# PC2_Input.net
KiCad netlist of a schematic drawn in Altium Designer
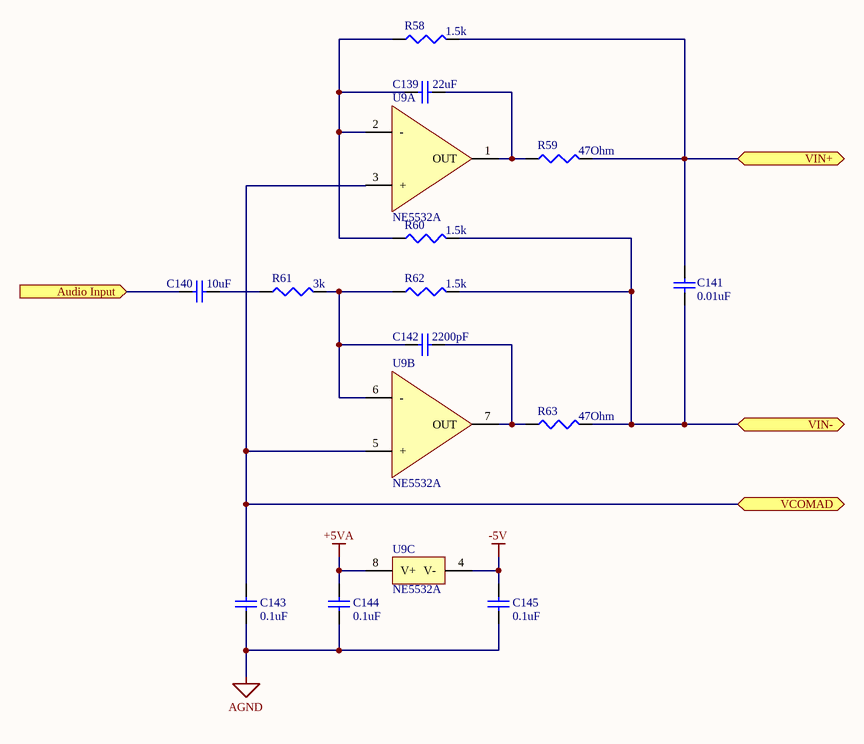
[diagram p0: PC2_Input.SchDoc]

(export (version "E")
  (design (tool "Eeschema 10.0.6"))
  (components
    (comp (ref "C139")
      (value "22uF")
      (footprint "CAPC1608X08")
      (description "Capacitor (Semiconductor SIM Model)")
      (libsource (lib "Michel") (part "Cap Semi"))
    )
    (comp (ref "C140")
      (value "10uF")
      (footprint "CAPC1608X08")
      (description "Capacitor (Semiconductor SIM Model)")
      (libsource (lib "Michel") (part "Cap Semi"))
    )
    (comp (ref "C141")
      (value "0.01uF")
      (footprint "CAPC1608X08")
      (description "Capacitor (Semiconductor SIM Model)")
      (fields (field (name "Comment") "Cap Semi"))
      (libsource (lib "Michel") (part "Cap Semi"))
    )
    (comp (ref "C142")
      (value "2200pF")
      (footprint "CAPC1608X08")
      (description "Capacitor (Semiconductor SIM Model)")
      (fields (field (name "Comment") "Cap Semi"))
      (libsource (lib "Michel") (part "Cap Semi"))
    )
    (comp (ref "C143")
      (value "0.1uF")
      (footprint "CAPC1608X08")
      (description "Capacitor (Semiconductor SIM Model)")
      (libsource (lib "Michel") (part "Cap Semi"))
    )
    (comp (ref "C144")
      (value "0.1uF")
      (footprint "CAPC1608X08")
      (description "Capacitor (Semiconductor SIM Model)")
      (libsource (lib "Michel") (part "Cap Semi"))
    )
    (comp (ref "C145")
      (value "0.1uF")
      (footprint "CAPC1608X08")
      (description "Capacitor (Semiconductor SIM Model)")
      (libsource (lib "Michel") (part "Cap Semi"))
    )
    (comp (ref "R58")
      (value "1.5k")
      (footprint "RESC1608X05")
      (description "Resistor")
      (fields (field (name "Comment") "Res3"))
      (libsource (lib "Michel") (part "Res3"))
    )
    (comp (ref "R59")
      (value "47Ohm")
      (footprint "RESC1608X05")
      (description "Resistor")
      (fields (field (name "Comment") "Res3"))
      (libsource (lib "Michel") (part "Res3"))
    )
    (comp (ref "R60")
      (value "1.5k")
      (footprint "RESC1608X05")
      (description "Resistor")
      (fields (field (name "Comment") "Res3"))
      (libsource (lib "Michel") (part "Res3"))
    )
    (comp (ref "R61")
      (value "3k")
      (footprint "RESC1608X05")
      (description "Resistor")
      (fields (field (name "Comment") "Res3"))
      (libsource (lib "Michel") (part "Res3"))
    )
    (comp (ref "R62")
      (value "1.5k")
      (footprint "RESC1608X05")
      (description "Resistor")
      (fields (field (name "Comment") "Res3"))
      (libsource (lib "Michel") (part "Res3"))
    )
    (comp (ref "R63")
      (value "47Ohm")
      (footprint "RESC1608X05")
      (description "Resistor")
      (fields (field (name "Comment") "Res3"))
      (libsource (lib "Michel") (part "Res3"))
    )
    (comp (ref "U9")
      (value "NE5532A")
      (footprint "D8-M")
      (description "Amplificateur Opérationnel")
      (libsource (lib "Michel") (part "NE5532A"))
    )
  )
  (nets
    (net (code "1") (name "+5VA") (class "Default")
      (node (ref "C144") (pin "1") (pinfunction "1_1") (pintype "passive"))
      (node (ref "U9") (pin "8") (pinfunction "V+_8") (pintype "passive"))
    )
    (net (code "2") (name "-5V") (class "Default")
      (node (ref "C145") (pin "1") (pinfunction "1_1") (pintype "passive"))
      (node (ref "U9") (pin "4") (pinfunction "V-_4") (pintype "passive"))
    )
    (net (code "3") (name "/Audio Input") (class "Default")
      (node (ref "C140") (pin "2") (pinfunction "2_2") (pintype "passive"))
    )
    (net (code "4") (name "/VCOMAD") (class "Default")
      (node (ref "C143") (pin "1") (pinfunction "1_1") (pintype "passive"))
      (node (ref "U9") (pin "3") (pinfunction "+_3") (pintype "passive"))
      (node (ref "U9") (pin "5") (pinfunction "+_5") (pintype "passive"))
    )
    (net (code "5") (name "/VIN+") (class "Default")
      (node (ref "C141") (pin "1") (pinfunction "1_1") (pintype "passive"))
      (node (ref "R58") (pin "2") (pinfunction "2_2") (pintype "passive"))
      (node (ref "R59") (pin "2") (pinfunction "2_2") (pintype "passive"))
    )
    (net (code "6") (name "/VIN-") (class "Default")
      (node (ref "C141") (pin "2") (pinfunction "2_2") (pintype "passive"))
      (node (ref "R60") (pin "2") (pinfunction "2_2") (pintype "passive"))
      (node (ref "R62") (pin "2") (pinfunction "2_2") (pintype "passive"))
      (node (ref "R63") (pin "2") (pinfunction "2_2") (pintype "passive"))
    )
    (net (code "7") (name "AGND") (class "Default")
      (node (ref "C143") (pin "2") (pinfunction "2_2") (pintype "passive"))
      (node (ref "C144") (pin "2") (pinfunction "2_2") (pintype "passive"))
      (node (ref "C145") (pin "2") (pinfunction "2_2") (pintype "passive"))
    )
    (net (code "8") (name "Net-(C140-Pad1)") (class "Default")
      (node (ref "C140") (pin "1") (pinfunction "1_1") (pintype "passive"))
      (node (ref "R61") (pin "1") (pinfunction "1_1") (pintype "passive"))
    )
    (net (code "9") (name "Net-(U9A--)") (class "Default")
      (node (ref "C139") (pin "2") (pinfunction "2_2") (pintype "passive"))
      (node (ref "R58") (pin "1") (pinfunction "1_1") (pintype "passive"))
      (node (ref "R60") (pin "1") (pinfunction "1_1") (pintype "passive"))
      (node (ref "U9") (pin "2") (pinfunction "-_2") (pintype "passive"))
    )
    (net (code "10") (name "Net-(U9A-OUT)") (class "Default")
      (node (ref "C139") (pin "1") (pinfunction "1_1") (pintype "passive"))
      (node (ref "R59") (pin "1") (pinfunction "1_1") (pintype "passive"))
      (node (ref "U9") (pin "1") (pinfunction "OUT_1") (pintype "passive"))
    )
    (net (code "11") (name "Net-(U9B--)") (class "Default")
      (node (ref "C142") (pin "2") (pinfunction "2_2") (pintype "passive"))
      (node (ref "R61") (pin "2") (pinfunction "2_2") (pintype "passive"))
      (node (ref "R62") (pin "1") (pinfunction "1_1") (pintype "passive"))
      (node (ref "U9") (pin "6") (pinfunction "-_6") (pintype "passive"))
    )
    (net (code "12") (name "Net-(U9B-OUT)") (class "Default")
      (node (ref "C142") (pin "1") (pinfunction "1_1") (pintype "passive"))
      (node (ref "R63") (pin "1") (pinfunction "1_1") (pintype "passive"))
      (node (ref "U9") (pin "7") (pinfunction "OUT_7") (pintype "passive"))
    )
  )
)
